# L298-guillaume.net
KiCad netlist of a schematic drawn in Altium Designer
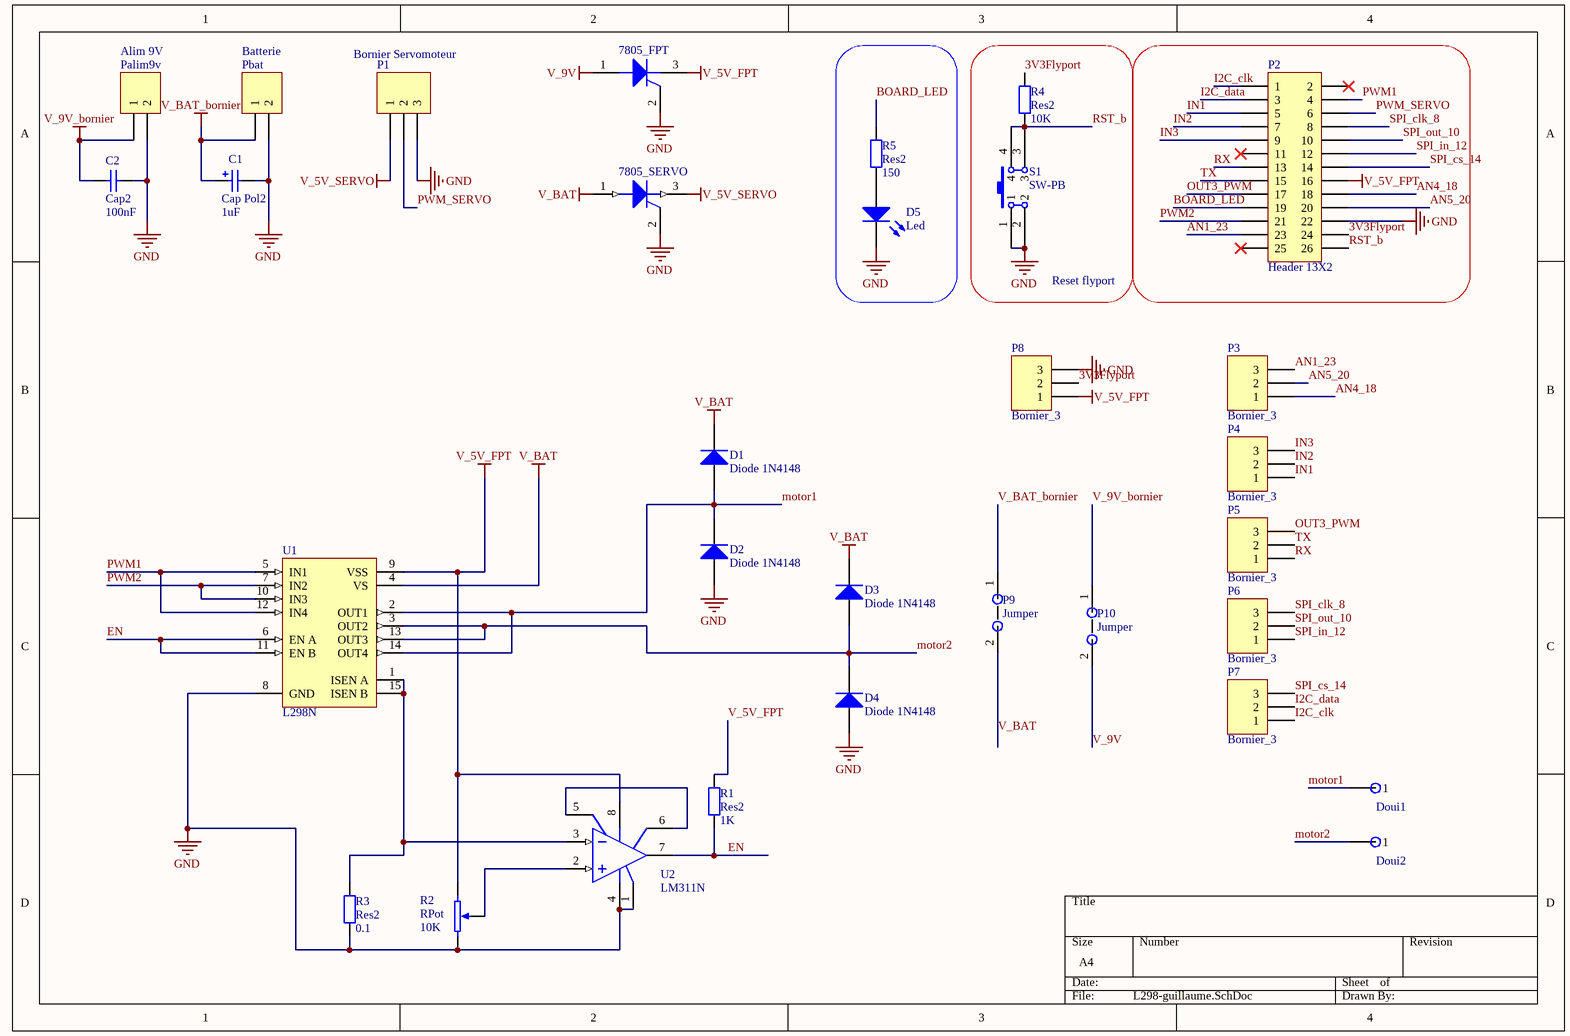
[diagram p0: L298-guillaume.SchDoc]

(export (version "E")
  (design (tool "Eeschema 10.0.6"))
  (components
    (comp (ref "7805_FPT")
      (value "SCR")
      (footprint "TO-220-AB")
      (description "Silicon Controlled Rectifier")
      (fields (field (name "PUBLISHER") "Altium Limited"))
      (libsource (lib "Miscellaneous Devices") (part "SCR"))
    )
    (comp (ref "7805_SERVO")
      (value "SCR")
      (footprint "TO-220-AB")
      (description "Silicon Controlled Rectifier")
      (fields (field (name "PUBLISHER") "Altium Limited"))
      (libsource (lib "Miscellaneous Devices") (part "SCR"))
    )
    (comp (ref "C1")
      (value "Cap Pol2")
      (footprint "Capa2_pol")
      (description "Polarized Capacitor (Radial)")
      (fields (field (name "ALTIUM_VALUE") "1uF") (field (name "PUBLISHER") "Altium Limited"))
      (libsource (lib "LIBRAIRIE_INTEGREE_PHELMA1") (part "Cap Pol2"))
    )
    (comp (ref "C2")
      (value "Cap2")
      (footprint "CAPA2")
      (description "Capacitor")
      (fields (field (name "ALTIUM_VALUE") "100nF") (field (name "PUBLISHER") "Altium Limited"))
      (libsource (lib "LIBRAIRIE_INTEGREE_PHELMA1") (part "Cap2"))
    )
    (comp (ref "D1")
      (value "Diode 1N4148")
      (footprint "Ddiode")
      (description "High Conductance Fast Diode")
      (fields (field (name "PUBLISHER") "Altium Limited"))
      (libsource (lib "LIBRAIRIE_INTEGREE_PHELMA1") (part "Diode 1N4148"))
    )
    (comp (ref "D2")
      (value "Diode 1N4148")
      (footprint "Ddiode")
      (description "High Conductance Fast Diode")
      (fields (field (name "PUBLISHER") "Altium Limited"))
      (libsource (lib "LIBRAIRIE_INTEGREE_PHELMA1") (part "Diode 1N4148"))
    )
    (comp (ref "D3")
      (value "Diode 1N4148")
      (footprint "Ddiode")
      (description "High Conductance Fast Diode")
      (fields (field (name "PUBLISHER") "Altium Limited"))
      (libsource (lib "LIBRAIRIE_INTEGREE_PHELMA1") (part "Diode 1N4148"))
    )
    (comp (ref "D4")
      (value "Diode 1N4148")
      (footprint "Ddiode")
      (description "High Conductance Fast Diode")
      (fields (field (name "PUBLISHER") "Altium Limited"))
      (libsource (lib "LIBRAIRIE_INTEGREE_PHELMA1") (part "Diode 1N4148"))
    )
    (comp (ref "D5")
      (value "Led")
      (footprint "LED")
      (description "LED")
      (fields (field (name "PUBLISHER") "Altium Limited"))
      (libsource (lib "LIBRAIRIE_INTEGREE_PHELMA1") (part "Led"))
    )
    (comp (ref "Doui1")
      (value "douille_2mm")
      (footprint "Douille-2mm")
      (description "1-Pin")
      (fields (field (name "PUBLISHER") "Altium Limited"))
      (libsource (lib "INTEGRATED_LIBRARY1_CONNECTEURS") (part "douille_2mm"))
    )
    (comp (ref "Doui2")
      (value "douille_2mm")
      (footprint "Douille-2mm")
      (description "1-Pin")
      (fields (field (name "PUBLISHER") "Altium Limited"))
      (libsource (lib "INTEGRATED_LIBRARY1_CONNECTEURS") (part "douille_2mm"))
    )
    (comp (ref "P1")
      (value "Bornier Servomoteur")
      (footprint "Bornier_3")
      (description "Header, 3-Pin")
      (fields (field (name "PUBLISHER") "Altium Limited"))
      (libsource (lib "") (part "Bornier_3_1"))
    )
    (comp (ref "P2")
      (value "Header 13X2")
      (footprint "HDR2X13")
      (description "Header, 13-Pin, Dual row")
      (fields (field (name "PUBLISHER") "Altium Limited"))
      (libsource (lib "Miscellaneous Connectors") (part "Header 13X2"))
    )
    (comp (ref "P3")
      (value "Bornier_3")
      (footprint "Bornier_3")
      (description "Header, 3-Pin")
      (fields (field (name "PUBLISHER") "Altium Limited"))
      (libsource (lib "INTEGRATED_LIBRARY1_CONNECTEURS") (part "Bornier_3"))
    )
    (comp (ref "P4")
      (value "Bornier_3")
      (footprint "Bornier_3")
      (description "Header, 3-Pin")
      (fields (field (name "PUBLISHER") "Altium Limited"))
      (libsource (lib "INTEGRATED_LIBRARY1_CONNECTEURS") (part "Bornier_3"))
    )
    (comp (ref "P5")
      (value "Bornier_3")
      (footprint "Bornier_3")
      (description "Header, 3-Pin")
      (fields (field (name "PUBLISHER") "Altium Limited"))
      (libsource (lib "INTEGRATED_LIBRARY1_CONNECTEURS") (part "Bornier_3"))
    )
    (comp (ref "P6")
      (value "Bornier_3")
      (footprint "Bornier_3")
      (description "Header, 3-Pin")
      (fields (field (name "PUBLISHER") "Altium Limited"))
      (libsource (lib "INTEGRATED_LIBRARY1_CONNECTEURS") (part "Bornier_3"))
    )
    (comp (ref "P7")
      (value "Bornier_3")
      (footprint "Bornier_3")
      (description "Header, 3-Pin")
      (fields (field (name "PUBLISHER") "Altium Limited"))
      (libsource (lib "INTEGRATED_LIBRARY1_CONNECTEURS") (part "Bornier_3"))
    )
    (comp (ref "P8")
      (value "Bornier_3")
      (footprint "Bornier_3")
      (description "Header, 3-Pin")
      (fields (field (name "PUBLISHER") "Altium Limited"))
      (libsource (lib "INTEGRATED_LIBRARY1_CONNECTEURS") (part "Bornier_3"))
    )
    (comp (ref "P9")
      (value "Jumper")
      (footprint "picot2")
      (fields (field (name "PUBLISHER") "Altium Limited"))
      (libsource (lib "INTEGRATED_LIBRARY1_CONNECTEURS") (part "Jumper"))
    )
    (comp (ref "P10")
      (value "Jumper")
      (footprint "picot2")
      (fields (field (name "PUBLISHER") "Altium Limited"))
      (libsource (lib "INTEGRATED_LIBRARY1_CONNECTEURS") (part "Jumper"))
    )
    (comp (ref "Palim9v")
      (value "Alim 9V")
      (footprint "Bornier_2")
      (description "Header, 2-Pin")
      (fields (field (name "PUBLISHER") "Altium Limited"))
      (libsource (lib "INTEGRATED_LIBRARY1_CONNECTEURS") (part "Bornier_2"))
    )
    (comp (ref "Pbat")
      (value "Batterie")
      (footprint "Bornier_2")
      (description "Header, 2-Pin")
      (fields (field (name "PUBLISHER") "Altium Limited"))
      (libsource (lib "INTEGRATED_LIBRARY1_CONNECTEURS") (part "Bornier_2"))
    )
    (comp (ref "R1")
      (value "Res2")
      (footprint "res5_1/4W")
      (description "Resistor")
      (fields (field (name "ALTIUM_VALUE") "1K") (field (name "PUBLISHER") "Altium Limited"))
      (libsource (lib "") (part "Res2_1"))
    )
    (comp (ref "R2")
      (value "RPot")
      (footprint "AJUSTABLE")
      (description "Potentiometer")
      (fields (field (name "ALTIUM_VALUE") "10K") (field (name "PUBLISHER") "Altium Limited"))
      (libsource (lib "LIBRAIRIE_INTEGREE_PHELMA1") (part "RPot"))
    )
    (comp (ref "R3")
      (value "Res2")
      (footprint "res5_1/4W")
      (description "Resistor")
      (fields (field (name "ALTIUM_VALUE") "0.1") (field (name "PUBLISHER") "Altium Limited"))
      (libsource (lib "LIBRAIRIE_INTEGREE_PHELMA1") (part "Res2"))
    )
    (comp (ref "R4")
      (value "Res2")
      (footprint "res5_1/4W")
      (description "Resistor")
      (fields (field (name "ALTIUM_VALUE") "10K") (field (name "PUBLISHER") "Altium Limited"))
      (libsource (lib "LIBRAIRIE_INTEGREE_PHELMA1") (part "Res2"))
    )
    (comp (ref "R5")
      (value "Res2")
      (footprint "res5_1/4W")
      (description "Resistor")
      (fields (field (name "ALTIUM_VALUE") "150") (field (name "PUBLISHER") "Altium Limited"))
      (libsource (lib "LIBRAIRIE_INTEGREE_PHELMA1") (part "Res2"))
    )
    (comp (ref "S1")
      (value "SW-PB")
      (footprint "SW_BP")
      (description "Switch")
      (fields (field (name "PUBLISHER") "Altium Limited"))
      (libsource (lib "INTEGRATED_LIBRARY1_CONNECTEURS") (part "SW-PB"))
    )
    (comp (ref "U1")
      (value "L298N")
      (footprint "Multiwatt15V")
      (description "Dual Full Bridge Driver")
      (fields (field (name "PUBLISHER") "Altium Limited"))
      (libsource (lib "ST Interface DC Motor Controller") (part "L298N"))
    )
    (comp (ref "U2")
      (value "LM311N")
      (footprint "DIP8")
      (description "Voltage Comparator")
      (fields (field (name "PUBLISHER") "Altium Limited"))
      (libsource (lib "LIBRAIRIE_INTEGREE_PHELMA1") (part "LM311N"))
    )
  )
  (nets
    (net (code "1") (name "/3V3Flyport") (class "Default")
      (node (ref "P2") (pin "24") (pinfunction "24_24") (pintype "passive"))
      (node (ref "P8") (pin "2") (pinfunction "2_2") (pintype "passive"))
      (node (ref "R4") (pin "1") (pinfunction "1_1") (pintype "passive"))
    )
    (net (code "2") (name "/AN1_23") (class "Default")
      (node (ref "P2") (pin "23") (pinfunction "23_23") (pintype "passive"))
      (node (ref "P3") (pin "3") (pinfunction "3_3") (pintype "passive"))
    )
    (net (code "3") (name "/AN4_18") (class "Default")
      (node (ref "P2") (pin "18") (pinfunction "18_18") (pintype "passive"))
      (node (ref "P3") (pin "1") (pinfunction "1_1") (pintype "passive"))
    )
    (net (code "4") (name "/AN5_20") (class "Default")
      (node (ref "P2") (pin "20") (pinfunction "20_20") (pintype "passive"))
      (node (ref "P3") (pin "2") (pinfunction "2_2") (pintype "passive"))
    )
    (net (code "5") (name "/BOARD_LED") (class "Default")
      (node (ref "P2") (pin "19") (pinfunction "19_19") (pintype "passive"))
      (node (ref "R5") (pin "1") (pinfunction "1_1") (pintype "passive"))
    )
    (net (code "6") (name "/EN") (class "Default")
      (node (ref "R1") (pin "1") (pinfunction "1_1") (pintype "passive"))
      (node (ref "U1") (pin "11") (pinfunction "EN_B_11") (pintype "input"))
      (node (ref "U1") (pin "6") (pinfunction "EN_A_6") (pintype "input"))
      (node (ref "U2") (pin "7") (pinfunction "OUT_7") (pintype "open_collector"))
    )
    (net (code "7") (name "/I2C_clk") (class "Default")
      (node (ref "P2") (pin "1") (pinfunction "1_1") (pintype "passive"))
      (node (ref "P7") (pin "1") (pinfunction "1_1") (pintype "passive"))
    )
    (net (code "8") (name "/I2C_data") (class "Default")
      (node (ref "P2") (pin "3") (pinfunction "3_3") (pintype "passive"))
      (node (ref "P7") (pin "2") (pinfunction "2_2") (pintype "passive"))
    )
    (net (code "9") (name "/IN1") (class "Default")
      (node (ref "P2") (pin "5") (pinfunction "5_5") (pintype "passive"))
      (node (ref "P4") (pin "1") (pinfunction "1_1") (pintype "passive"))
    )
    (net (code "10") (name "/IN2") (class "Default")
      (node (ref "P2") (pin "7") (pinfunction "7_7") (pintype "passive"))
      (node (ref "P4") (pin "2") (pinfunction "2_2") (pintype "passive"))
    )
    (net (code "11") (name "/IN3") (class "Default")
      (node (ref "P2") (pin "9") (pinfunction "9_9") (pintype "passive"))
      (node (ref "P4") (pin "3") (pinfunction "3_3") (pintype "passive"))
    )
    (net (code "12") (name "/OUT3_PWM") (class "Default")
      (node (ref "P2") (pin "17") (pinfunction "17_17") (pintype "passive"))
      (node (ref "P5") (pin "3") (pinfunction "3_3") (pintype "passive"))
    )
    (net (code "13") (name "/PWM1") (class "Default")
      (node (ref "P2") (pin "4") (pinfunction "4_4") (pintype "passive"))
      (node (ref "U1") (pin "12") (pinfunction "IN4_12") (pintype "input"))
      (node (ref "U1") (pin "5") (pinfunction "IN1_5") (pintype "input"))
    )
    (net (code "14") (name "/PWM2") (class "Default")
      (node (ref "P2") (pin "21") (pinfunction "21_21") (pintype "passive"))
      (node (ref "U1") (pin "10") (pinfunction "IN3_10") (pintype "input"))
      (node (ref "U1") (pin "7") (pinfunction "IN2_7") (pintype "input"))
    )
    (net (code "15") (name "/PWM_SERVO") (class "Default")
      (node (ref "P1") (pin "2") (pinfunction "2_2") (pintype "passive"))
      (node (ref "P2") (pin "6") (pinfunction "6_6") (pintype "passive"))
    )
    (net (code "16") (name "/RST_b") (class "Default")
      (node (ref "P2") (pin "26") (pinfunction "26_26") (pintype "passive"))
      (node (ref "R4") (pin "2") (pinfunction "2_2") (pintype "passive"))
      (node (ref "S1") (pin "3") (pinfunction "3_3") (pintype "passive"))
      (node (ref "S1") (pin "4") (pinfunction "4_4") (pintype "passive"))
    )
    (net (code "17") (name "/RX") (class "Default")
      (node (ref "P2") (pin "13") (pinfunction "13_13") (pintype "passive"))
      (node (ref "P5") (pin "1") (pinfunction "1_1") (pintype "passive"))
    )
    (net (code "18") (name "/SPI_clk_8") (class "Default")
      (node (ref "P2") (pin "8") (pinfunction "8_8") (pintype "passive"))
      (node (ref "P6") (pin "3") (pinfunction "3_3") (pintype "passive"))
    )
    (net (code "19") (name "/SPI_cs_14") (class "Default")
      (node (ref "P2") (pin "14") (pinfunction "14_14") (pintype "passive"))
      (node (ref "P7") (pin "3") (pinfunction "3_3") (pintype "passive"))
    )
    (net (code "20") (name "/SPI_in_12") (class "Default")
      (node (ref "P2") (pin "12") (pinfunction "12_12") (pintype "passive"))
      (node (ref "P6") (pin "1") (pinfunction "1_1") (pintype "passive"))
    )
    (net (code "21") (name "/SPI_out_10") (class "Default")
      (node (ref "P2") (pin "10") (pinfunction "10_10") (pintype "passive"))
      (node (ref "P6") (pin "2") (pinfunction "2_2") (pintype "passive"))
    )
    (net (code "22") (name "/TX") (class "Default")
      (node (ref "P2") (pin "15") (pinfunction "15_15") (pintype "passive"))
      (node (ref "P5") (pin "2") (pinfunction "2_2") (pintype "passive"))
    )
    (net (code "23") (name "/motor1") (class "Default")
      (node (ref "D1") (pin "1") (pinfunction "A_1") (pintype "passive"))
      (node (ref "D2") (pin "2") (pinfunction "K_2") (pintype "passive"))
      (node (ref "Doui1") (pin "1") (pinfunction "1_1") (pintype "passive"))
      (node (ref "U1") (pin "14") (pinfunction "OUT4_14") (pintype "output"))
      (node (ref "U1") (pin "2") (pinfunction "OUT1_2") (pintype "output"))
    )
    (net (code "24") (name "/motor2") (class "Default")
      (node (ref "D3") (pin "1") (pinfunction "A_1") (pintype "passive"))
      (node (ref "D4") (pin "2") (pinfunction "K_2") (pintype "passive"))
      (node (ref "Doui2") (pin "1") (pinfunction "1_1") (pintype "passive"))
      (node (ref "U1") (pin "13") (pinfunction "OUT3_13") (pintype "output"))
      (node (ref "U1") (pin "3") (pinfunction "OUT2_3") (pintype "output"))
    )
    (net (code "25") (name "GND") (class "Default")
      (node (ref "7805_FPT") (pin "2") (pinfunction "GND_2") (pintype "power_in"))
      (node (ref "7805_SERVO") (pin "2") (pinfunction "GND_2") (pintype "power_in"))
      (node (ref "C1") (pin "2") (pinfunction "2_2") (pintype "passive"))
      (node (ref "C2") (pin "2") (pinfunction "2_2") (pintype "passive"))
      (node (ref "D2") (pin "1") (pinfunction "A_1") (pintype "passive"))
      (node (ref "D4") (pin "1") (pinfunction "A_1") (pintype "passive"))
      (node (ref "D5") (pin "2") (pinfunction "K_2") (pintype "passive"))
      (node (ref "P1") (pin "3") (pinfunction "3_3") (pintype "passive"))
      (node (ref "P2") (pin "22") (pinfunction "22_22") (pintype "passive"))
      (node (ref "P8") (pin "3") (pinfunction "3_3") (pintype "passive"))
      (node (ref "Palim9v") (pin "2") (pinfunction "2_2") (pintype "passive"))
      (node (ref "Pbat") (pin "2") (pinfunction "2_2") (pintype "passive"))
      (node (ref "R2") (pin "3") (pinfunction "TOP_3") (pintype "passive"))
      (node (ref "R3") (pin "2") (pinfunction "2_2") (pintype "passive"))
      (node (ref "S1") (pin "1") (pinfunction "1_1") (pintype "passive"))
      (node (ref "S1") (pin "2") (pinfunction "2_2") (pintype "passive"))
      (node (ref "U1") (pin "8") (pinfunction "GND_8") (pintype "power_in"))
      (node (ref "U2") (pin "1") (pinfunction "GND_1") (pintype "power_in"))
      (node (ref "U2") (pin "4") (pinfunction "V-_(CASE)_4") (pintype "power_in"))
    )
    (net (code "26") (name "Net-(D5-A)") (class "Default")
      (node (ref "D5") (pin "1") (pinfunction "A_1") (pintype "passive"))
      (node (ref "R5") (pin "2") (pinfunction "2_2") (pintype "passive"))
    )
    (net (code "27") (name "Net-(R2-TAP)") (class "Default")
      (node (ref "R2") (pin "2") (pinfunction "TAP_2") (pintype "passive"))
      (node (ref "U2") (pin "2") (pinfunction "IN+_2") (pintype "input"))
    )
    (net (code "28") (name "Net-(U1-ISEN_A)") (class "Default")
      (node (ref "R3") (pin "1") (pinfunction "1_1") (pintype "passive"))
      (node (ref "U1") (pin "1") (pinfunction "ISEN_A_1") (pintype "passive"))
      (node (ref "U1") (pin "15") (pinfunction "ISEN_B_15") (pintype "passive"))
      (node (ref "U2") (pin "3") (pinfunction "IN-_3") (pintype "input"))
    )
    (net (code "29") (name "Net-(U2-BAL)") (class "Default")
      (node (ref "U2") (pin "5") (pinfunction "BAL_5") (pintype "passive"))
      (node (ref "U2") (pin "6") (pinfunction "BAL/STB_6") (pintype "passive"))
    )
    (net (code "30") (name "V_5V_FPT") (class "Default")
      (node (ref "7805_FPT") (pin "3") (pinfunction "OUT_3") (pintype "power_in"))
      (node (ref "P2") (pin "16") (pinfunction "16_16") (pintype "passive"))
      (node (ref "P8") (pin "1") (pinfunction "1_1") (pintype "passive"))
      (node (ref "R1") (pin "2") (pinfunction "2_2") (pintype "passive"))
      (node (ref "R2") (pin "1") (pinfunction "BOT_1") (pintype "passive"))
      (node (ref "U1") (pin "9") (pinfunction "VSS_9") (pintype "power_in"))
      (node (ref "U2") (pin "8") (pinfunction "V+_8") (pintype "power_in"))
    )
    (net (code "31") (name "V_5V_SERVO") (class "Default")
      (node (ref "7805_SERVO") (pin "3") (pinfunction "OUT_3") (pintype "power_in"))
      (node (ref "P1") (pin "1") (pinfunction "1_1") (pintype "passive"))
    )
    (net (code "32") (name "V_9V") (class "Default")
      (node (ref "7805_FPT") (pin "1") (pinfunction "IN_1") (pintype "power_in"))
      (node (ref "P10") (pin "2") (pinfunction "2_2") (pintype "passive"))
    )
    (net (code "33") (name "V_9V_bornier") (class "Default")
      (node (ref "C2") (pin "1") (pinfunction "1_1") (pintype "passive"))
      (node (ref "P10") (pin "1") (pinfunction "1_1") (pintype "passive"))
      (node (ref "Palim9v") (pin "1") (pinfunction "1_1") (pintype "passive"))
    )
    (net (code "34") (name "V_BAT") (class "Default")
      (node (ref "7805_SERVO") (pin "1") (pinfunction "IN_1") (pintype "power_in"))
      (node (ref "D1") (pin "2") (pinfunction "K_2") (pintype "passive"))
      (node (ref "D3") (pin "2") (pinfunction "K_2") (pintype "passive"))
      (node (ref "P9") (pin "2") (pinfunction "2_2") (pintype "passive"))
      (node (ref "U1") (pin "4") (pinfunction "VS_4") (pintype "power_in"))
    )
    (net (code "35") (name "V_BAT_bornier") (class "Default")
      (node (ref "C1") (pin "1") (pinfunction "1_1") (pintype "passive"))
      (node (ref "P9") (pin "1") (pinfunction "1_1") (pintype "passive"))
      (node (ref "Pbat") (pin "1") (pinfunction "1_1") (pintype "passive"))
    )
    (net (code "36") (name "unconnected-(P2-Pad2)") (class "Default")
      (node (ref "P2") (pin "2") (pinfunction "2_2") (pintype "passive+no_connect"))
    )
    (net (code "37") (name "unconnected-(P2-Pad11)") (class "Default")
      (node (ref "P2") (pin "11") (pinfunction "11_11") (pintype "passive+no_connect"))
    )
    (net (code "38") (name "unconnected-(P2-Pad25)") (class "Default")
      (node (ref "P2") (pin "25") (pinfunction "25_25") (pintype "passive+no_connect"))
    )
  )
)
